# zx81_SD_11.net
KiCad netlist of a schematic drawn in EAGLE
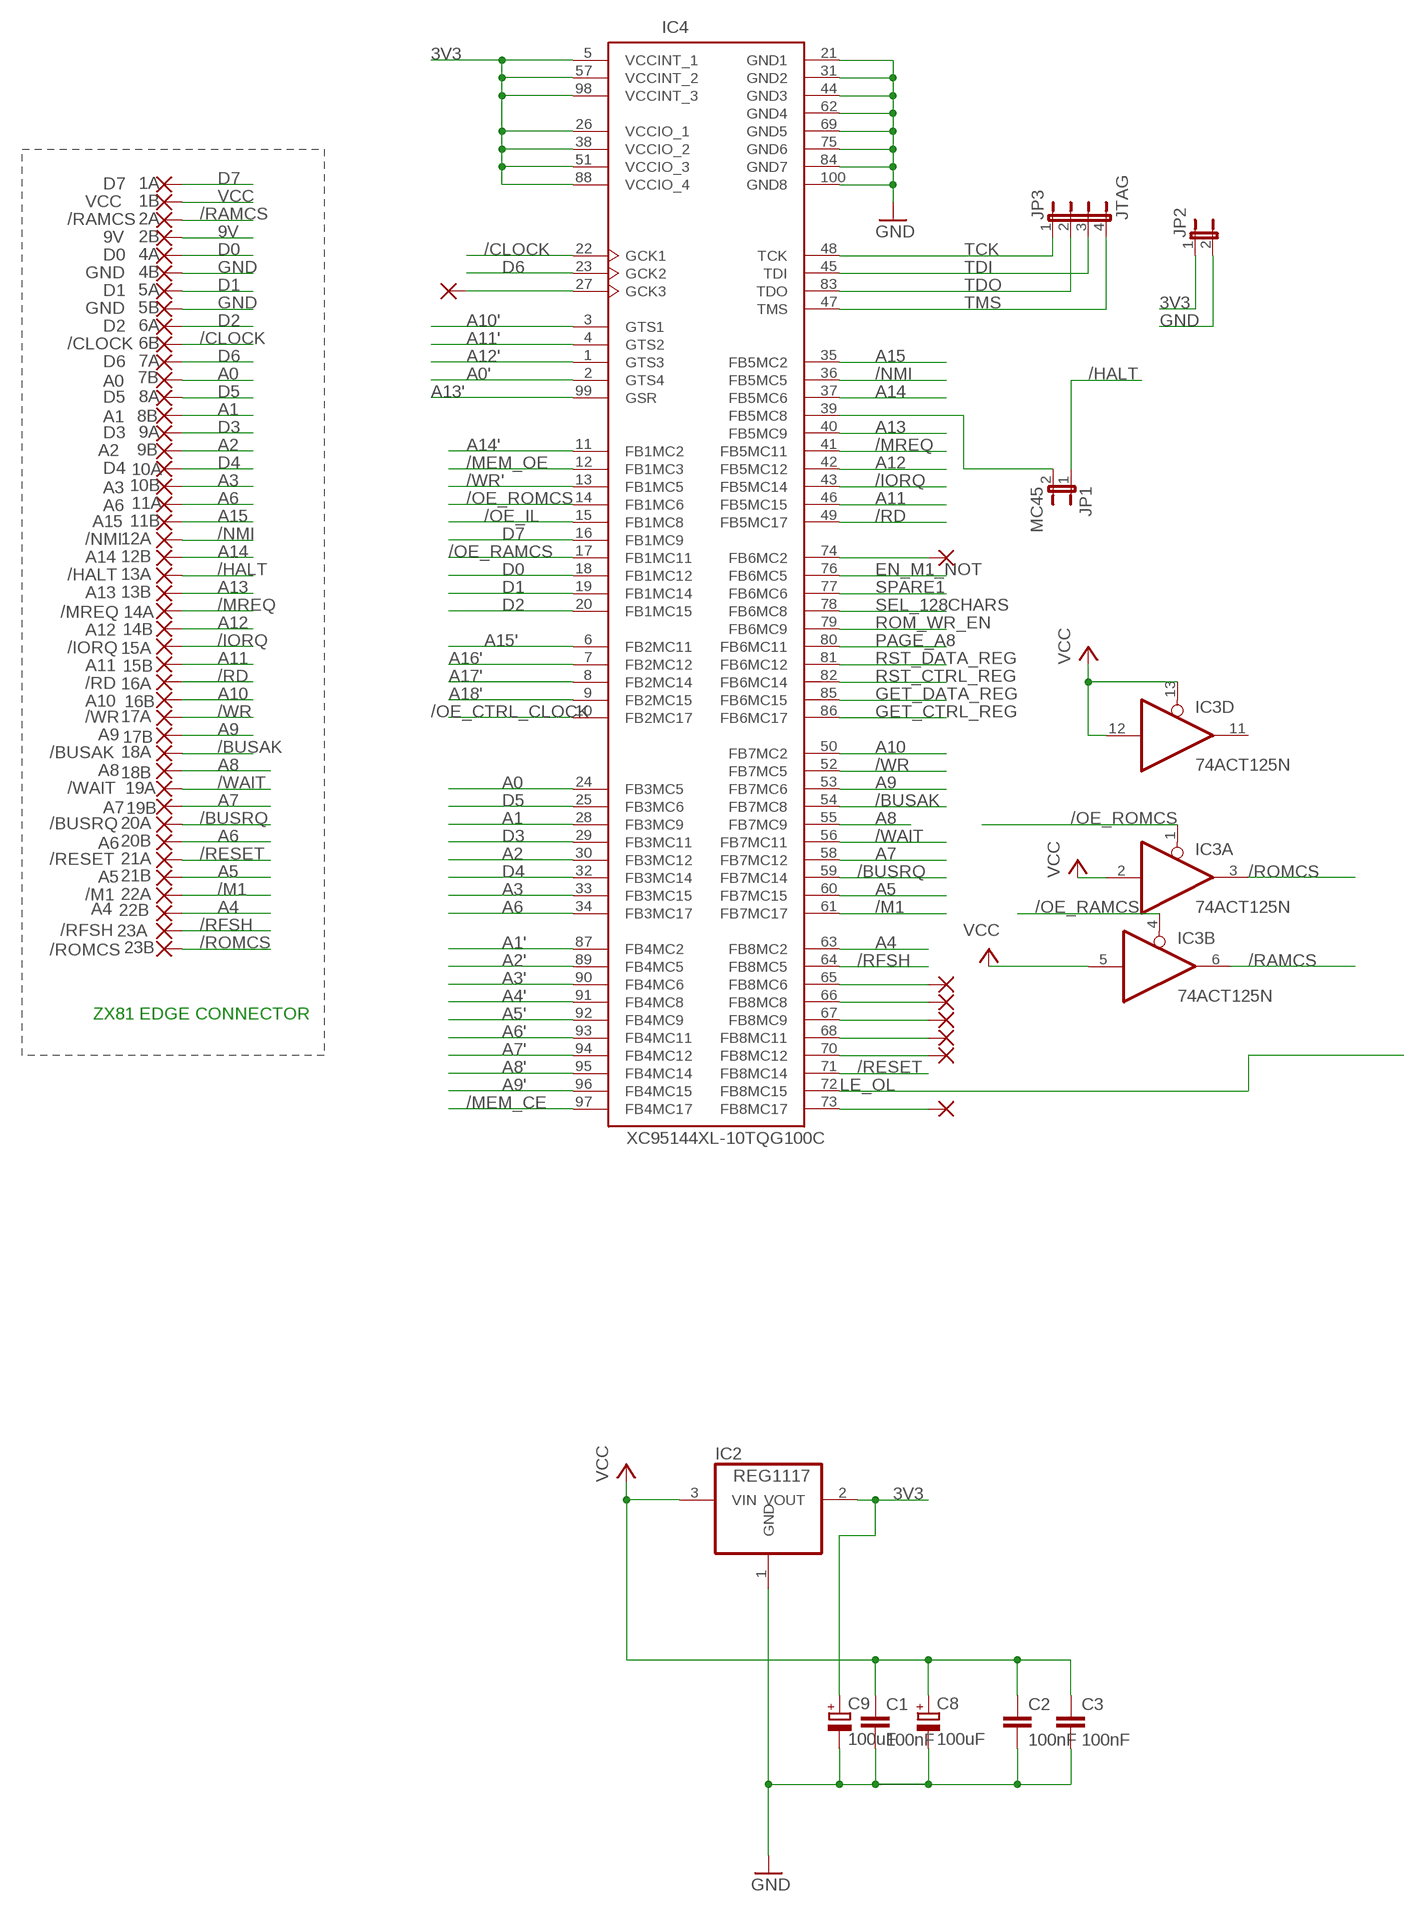
[diagram p0: schematic, sheet 1, part 1 of 2]
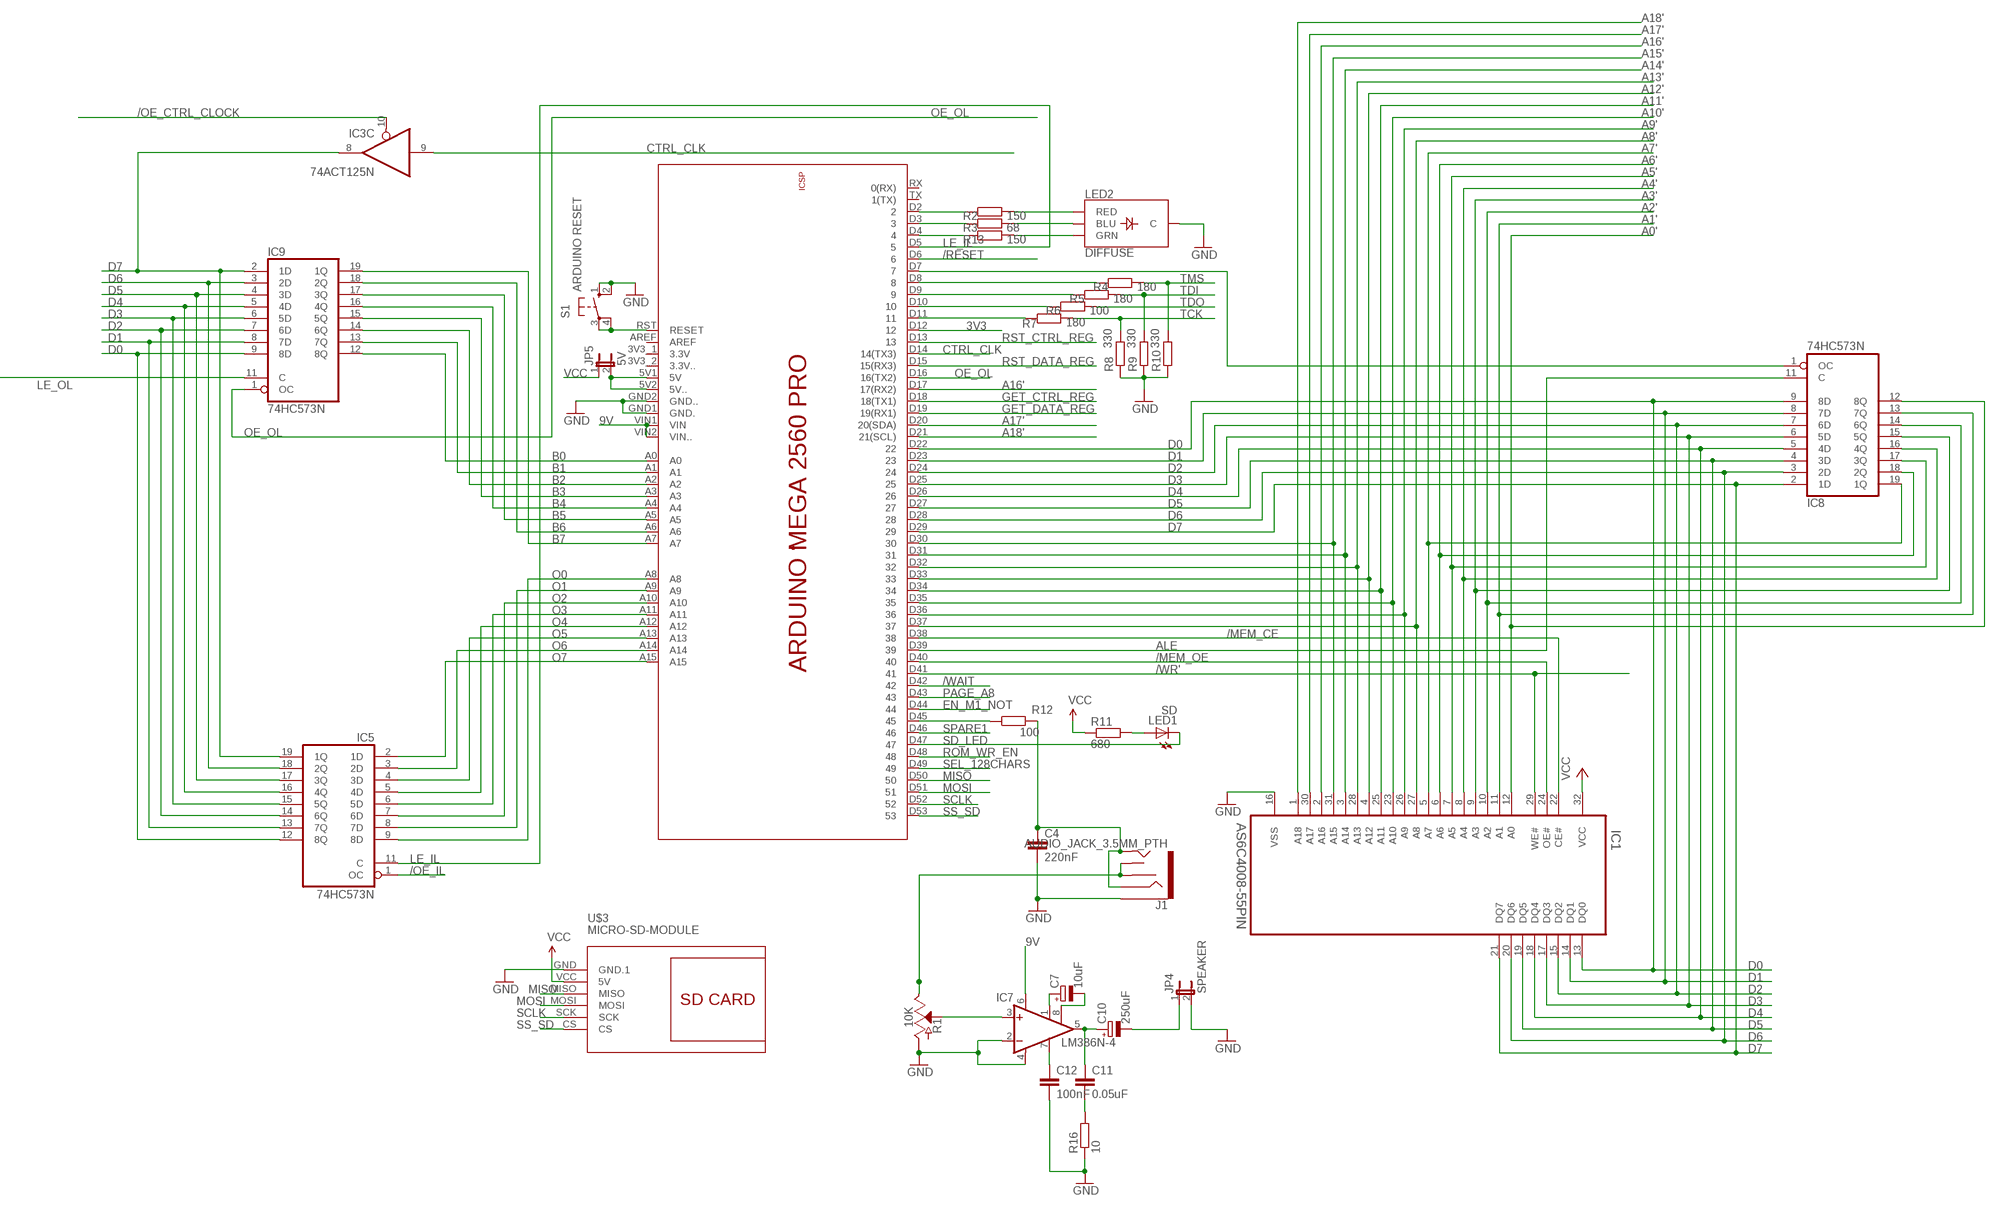
[diagram p1: schematic, sheet 1, part 2 of 2]

(export (version "E")
  (design (tool "Eeschema 10.0.6"))
  (components
    (comp (ref "1A")
      (value "D7")
      (footprint "eagle-import:EDGEPIN")
      (libsource (lib "eagle-import") (part "SMD2EDGEPIN"))
    )
    (comp (ref "1B")
      (value "VCC")
      (footprint "eagle-import:EDGEPIN")
      (libsource (lib "eagle-import") (part "SMD2EDGEPIN"))
    )
    (comp (ref "2A")
      (value "/RAMCS")
      (footprint "eagle-import:EDGEPIN")
      (libsource (lib "eagle-import") (part "SMD2EDGEPIN"))
    )
    (comp (ref "2B")
      (value "9V")
      (footprint "eagle-import:EDGEPIN")
      (libsource (lib "eagle-import") (part "SMD2EDGEPIN"))
    )
    (comp (ref "4A")
      (value "D0")
      (footprint "eagle-import:EDGEPIN")
      (libsource (lib "eagle-import") (part "SMD2EDGEPIN"))
    )
    (comp (ref "4B")
      (value "GND")
      (footprint "eagle-import:EDGEPIN")
      (libsource (lib "eagle-import") (part "SMD2EDGEPIN"))
    )
    (comp (ref "5A")
      (value "D1")
      (footprint "eagle-import:EDGEPIN")
      (libsource (lib "eagle-import") (part "SMD2EDGEPIN"))
    )
    (comp (ref "5B")
      (value "GND")
      (footprint "eagle-import:EDGEPIN")
      (libsource (lib "eagle-import") (part "SMD2EDGEPIN"))
    )
    (comp (ref "6A")
      (value "D2")
      (footprint "eagle-import:EDGEPIN")
      (libsource (lib "eagle-import") (part "SMD2EDGEPIN"))
    )
    (comp (ref "6B")
      (value "/CLOCK")
      (footprint "eagle-import:EDGEPIN")
      (libsource (lib "eagle-import") (part "SMD2EDGEPIN"))
    )
    (comp (ref "7A")
      (value "D6")
      (footprint "eagle-import:EDGEPIN")
      (libsource (lib "eagle-import") (part "SMD2EDGEPIN"))
    )
    (comp (ref "7B")
      (value "A0")
      (footprint "eagle-import:EDGEPIN")
      (libsource (lib "eagle-import") (part "SMD2EDGEPIN"))
    )
    (comp (ref "8A")
      (value "D5")
      (footprint "eagle-import:EDGEPIN")
      (libsource (lib "eagle-import") (part "SMD2EDGEPIN"))
    )
    (comp (ref "8B")
      (value "A1")
      (footprint "eagle-import:EDGEPIN")
      (libsource (lib "eagle-import") (part "SMD2EDGEPIN"))
    )
    (comp (ref "9A")
      (value "D3")
      (footprint "eagle-import:EDGEPIN")
      (libsource (lib "eagle-import") (part "SMD2EDGEPIN"))
    )
    (comp (ref "9B")
      (value "A2")
      (footprint "eagle-import:EDGEPIN")
      (libsource (lib "eagle-import") (part "SMD2EDGEPIN"))
    )
    (comp (ref "10A")
      (value "D4")
      (footprint "eagle-import:EDGEPIN")
      (libsource (lib "eagle-import") (part "SMD2EDGEPIN"))
    )
    (comp (ref "10B")
      (value "A3")
      (footprint "eagle-import:EDGEPIN")
      (libsource (lib "eagle-import") (part "SMD2EDGEPIN"))
    )
    (comp (ref "11A")
      (value "A6")
      (footprint "eagle-import:EDGEPIN")
      (libsource (lib "eagle-import") (part "SMD2EDGEPIN"))
    )
    (comp (ref "11B")
      (value "A15")
      (footprint "eagle-import:EDGEPIN")
      (libsource (lib "eagle-import") (part "SMD2EDGEPIN"))
    )
    (comp (ref "12A")
      (value "/NMI")
      (footprint "eagle-import:EDGEPIN")
      (libsource (lib "eagle-import") (part "SMD2EDGEPIN"))
    )
    (comp (ref "12B")
      (value "A14")
      (footprint "eagle-import:EDGEPIN")
      (libsource (lib "eagle-import") (part "SMD2EDGEPIN"))
    )
    (comp (ref "13A")
      (value "/HALT")
      (footprint "eagle-import:EDGEPIN")
      (libsource (lib "eagle-import") (part "SMD2EDGEPIN"))
    )
    (comp (ref "13B")
      (value "A13")
      (footprint "eagle-import:EDGEPIN")
      (libsource (lib "eagle-import") (part "SMD2EDGEPIN"))
    )
    (comp (ref "14A")
      (value "/MREQ")
      (footprint "eagle-import:EDGEPIN")
      (libsource (lib "eagle-import") (part "SMD2EDGEPIN"))
    )
    (comp (ref "14B")
      (value "A12")
      (footprint "eagle-import:EDGEPIN")
      (libsource (lib "eagle-import") (part "SMD2EDGEPIN"))
    )
    (comp (ref "15A")
      (value "/IORQ")
      (footprint "eagle-import:EDGEPIN")
      (libsource (lib "eagle-import") (part "SMD2EDGEPIN"))
    )
    (comp (ref "15B")
      (value "A11")
      (footprint "eagle-import:EDGEPIN")
      (libsource (lib "eagle-import") (part "SMD2EDGEPIN"))
    )
    (comp (ref "16A")
      (value "/RD")
      (footprint "eagle-import:EDGEPIN")
      (libsource (lib "eagle-import") (part "SMD2EDGEPIN"))
    )
    (comp (ref "16B")
      (value "A10")
      (footprint "eagle-import:EDGEPIN")
      (libsource (lib "eagle-import") (part "SMD2EDGEPIN"))
    )
    (comp (ref "17A")
      (value "/WR")
      (footprint "eagle-import:EDGEPIN")
      (libsource (lib "eagle-import") (part "SMD2EDGEPIN"))
    )
    (comp (ref "17B")
      (value "A9")
      (footprint "eagle-import:EDGEPIN")
      (libsource (lib "eagle-import") (part "SMD2EDGEPIN"))
    )
    (comp (ref "18A")
      (value "/BUSAK")
      (footprint "eagle-import:EDGEPIN")
      (libsource (lib "eagle-import") (part "SMD2EDGEPIN"))
    )
    (comp (ref "18B")
      (value "A8")
      (footprint "eagle-import:EDGEPIN")
      (libsource (lib "eagle-import") (part "SMD2EDGEPIN"))
    )
    (comp (ref "19A")
      (value "/WAIT")
      (footprint "eagle-import:EDGEPIN")
      (libsource (lib "eagle-import") (part "SMD2EDGEPIN"))
    )
    (comp (ref "19B")
      (value "A7")
      (footprint "eagle-import:EDGEPIN")
      (libsource (lib "eagle-import") (part "SMD2EDGEPIN"))
    )
    (comp (ref "20A")
      (value "/BUSRQ")
      (footprint "eagle-import:EDGEPIN")
      (libsource (lib "eagle-import") (part "SMD2EDGEPIN"))
    )
    (comp (ref "20B")
      (value "A6")
      (footprint "eagle-import:EDGEPIN")
      (libsource (lib "eagle-import") (part "SMD2EDGEPIN"))
    )
    (comp (ref "21A")
      (value "/RESET")
      (footprint "eagle-import:EDGEPIN")
      (libsource (lib "eagle-import") (part "SMD2EDGEPIN"))
    )
    (comp (ref "21B")
      (value "A5")
      (footprint "eagle-import:EDGEPIN")
      (libsource (lib "eagle-import") (part "SMD2EDGEPIN"))
    )
    (comp (ref "22A")
      (value "/M1")
      (footprint "eagle-import:EDGEPIN")
      (libsource (lib "eagle-import") (part "SMD2EDGEPIN"))
    )
    (comp (ref "22B")
      (value "A4")
      (footprint "eagle-import:EDGEPIN")
      (libsource (lib "eagle-import") (part "SMD2EDGEPIN"))
    )
    (comp (ref "23A")
      (value "/RFSH")
      (footprint "eagle-import:EDGEPIN")
      (libsource (lib "eagle-import") (part "SMD2EDGEPIN"))
    )
    (comp (ref "23B")
      (value "/ROMCS")
      (footprint "eagle-import:EDGEPIN")
      (libsource (lib "eagle-import") (part "SMD2EDGEPIN"))
    )
    (comp (ref "C1")
      (value "100nF")
      (footprint "eagle-import:C025-040X050")
      (libsource (lib "eagle-import") (part "C-EU025-040X050"))
    )
    (comp (ref "C2")
      (value "100nF")
      (footprint "eagle-import:C025-040X050")
      (libsource (lib "eagle-import") (part "C-EU025-040X050"))
    )
    (comp (ref "C3")
      (value "100nF")
      (footprint "eagle-import:C025-040X050")
      (libsource (lib "eagle-import") (part "C-EU025-040X050"))
    )
    (comp (ref "C4")
      (value "220nF")
      (footprint "eagle-import:C025-040X050")
      (libsource (lib "eagle-import") (part "C-EU025-040X050"))
    )
    (comp (ref "C7")
      (value "10uF")
      (footprint "eagle-import:E2-5")
      (libsource (lib "eagle-import") (part "CPOL-EUE2-5"))
    )
    (comp (ref "C8")
      (value "100uF")
      (footprint "eagle-import:E2-5")
      (libsource (lib "eagle-import") (part "CPOL-EUE2-5"))
    )
    (comp (ref "C9")
      (value "100uF")
      (footprint "eagle-import:E2-5")
      (libsource (lib "eagle-import") (part "CPOL-EUE2-5"))
    )
    (comp (ref "C10")
      (value "250uF")
      (footprint "eagle-import:E2-5")
      (libsource (lib "eagle-import") (part "CPOL-EUE2-5"))
    )
    (comp (ref "C11")
      (value "0.05uF")
      (footprint "eagle-import:C025-040X050")
      (libsource (lib "eagle-import") (part "C-EU025-040X050"))
    )
    (comp (ref "C12")
      (value "100nF")
      (footprint "eagle-import:C025-040X050")
      (libsource (lib "eagle-import") (part "C-EU025-040X050"))
    )
    (comp (ref "IC1")
      (value "AS6C4008-55PIN")
      (footprint "eagle-import:DIP1524W45P254L4203H406Q32")
      (fields (field (name "MF") "Alliance"))
      (libsource (lib "eagle-import") (part "AS6C4008-55PIN"))
    )
    (comp (ref "IC2")
      (value "REG1117")
      (footprint "eagle-import:SOT223")
      (libsource (lib "eagle-import") (part "REG1117"))
    )
    (comp (ref "IC3")
      (value "74ACT125N")
      (footprint "eagle-import:DIL14")
      (libsource (lib "eagle-import") (part "74125NACT"))
    )
    (comp (ref "IC4")
      (value "XC95144XL-10TQG100C")
      (footprint "eagle-import:TQFP100")
      (fields (field (name "MF") "Xilinx Inc."))
      (libsource (lib "eagle-import") (part "XC95144XL-10TQG100C"))
    )
    (comp (ref "IC5")
      (value "74HC573N")
      (footprint "eagle-import:DIL20")
      (libsource (lib "eagle-import") (part "74573NHC"))
    )
    (comp (ref "IC7")
      (value "LM386N-4")
      (footprint "eagle-import:DIL08")
      (libsource (lib "eagle-import") (part "LM386?-N4"))
    )
    (comp (ref "IC8")
      (value "74HC573N")
      (footprint "eagle-import:DIL20")
      (libsource (lib "eagle-import") (part "74573NHC"))
    )
    (comp (ref "IC9")
      (value "74HC573N")
      (footprint "eagle-import:DIL20")
      (libsource (lib "eagle-import") (part "74573NHC"))
    )
    (comp (ref "J1")
      (value "AUDIO_JACK_3.5MM_PTH")
      (footprint "eagle-import:AUDIO-JACK")
      (libsource (lib "eagle-import") (part "AUDIO_JACK_3.5MM_PTH"))
    )
    (comp (ref "JP1")
      (value "MC45")
      (footprint "eagle-import:JP1")
      (libsource (lib "eagle-import") (part "JP1E"))
    )
    (comp (ref "JP2")
      (value "JP1E")
      (footprint "eagle-import:JP1")
      (libsource (lib "eagle-import") (part "JP1E"))
    )
    (comp (ref "JP3")
      (value "JTAG")
      (footprint "eagle-import:JP4")
      (libsource (lib "eagle-import") (part "JP4E"))
    )
    (comp (ref "JP4")
      (value "SPEAKER")
      (footprint "eagle-import:JP1")
      (libsource (lib "eagle-import") (part "JP1E"))
    )
    (comp (ref "JP5")
      (value "5V")
      (footprint "eagle-import:JP1")
      (libsource (lib "eagle-import") (part "JP1E"))
    )
    (comp (ref "LED1")
      (value "SD")
      (footprint "eagle-import:LED5MM")
      (libsource (lib "eagle-import") (part "LED5MM"))
    )
    (comp (ref "LED2")
      (value "DIFFUSE")
      (footprint "eagle-import:LED-RGB-THRU")
      (libsource (lib "eagle-import") (part "LED-RGB-CCDIFFUSE"))
    )
    (comp (ref "PAD1")
      (value "1,6/0,8")
      (footprint "eagle-import:1,6_0,8")
      (libsource (lib "eagle-import") (part "1,6/0,8"))
    )
    (comp (ref "PAD2")
      (value "1,6/0,8")
      (footprint "eagle-import:1,6_0,8")
      (libsource (lib "eagle-import") (part "1,6/0,8"))
    )
    (comp (ref "PAD3")
      (value "1,6/0,8")
      (footprint "eagle-import:1,6_0,8")
      (libsource (lib "eagle-import") (part "1,6/0,8"))
    )
    (comp (ref "PAD4")
      (value "1,6/0,8")
      (footprint "eagle-import:1,6_0,8")
      (libsource (lib "eagle-import") (part "1,6/0,8"))
    )
    (comp (ref "PAD5")
      (value "1,6/0,8")
      (footprint "eagle-import:1,6_0,8")
      (libsource (lib "eagle-import") (part "1,6/0,8"))
    )
    (comp (ref "PAD6")
      (value "1,6/0,8")
      (footprint "eagle-import:1,6_0,8")
      (libsource (lib "eagle-import") (part "1,6/0,8"))
    )
    (comp (ref "PAD7")
      (value "1,6/0,8")
      (footprint "eagle-import:1,6_0,8")
      (libsource (lib "eagle-import") (part "1,6/0,8"))
    )
    (comp (ref "PAD8")
      (value "1,6/0,8")
      (footprint "eagle-import:1,6_0,8")
      (libsource (lib "eagle-import") (part "1,6/0,8"))
    )
    (comp (ref "R1")
      (value "10K")
      (footprint "eagle-import:POT-WHEEL")
      (libsource (lib "eagle-import") (part "POT"))
    )
    (comp (ref "R2")
      (value "150")
      (footprint "eagle-import:0204_7")
      (libsource (lib "eagle-import") (part "rcl_334_R-EU_0204/7"))
    )
    (comp (ref "R3")
      (value "68")
      (footprint "eagle-import:0204_7")
      (libsource (lib "eagle-import") (part "rcl_334_R-EU_0204/7"))
    )
    (comp (ref "R4")
      (value "180")
      (footprint "eagle-import:0204_7")
      (libsource (lib "eagle-import") (part "rcl_334_R-EU_0204/7"))
    )
    (comp (ref "R5")
      (value "180")
      (footprint "eagle-import:0204_7")
      (libsource (lib "eagle-import") (part "rcl_334_R-EU_0204/7"))
    )
    (comp (ref "R6")
      (value "100")
      (footprint "eagle-import:0204_7")
      (libsource (lib "eagle-import") (part "rcl_334_R-EU_0204/7"))
    )
    (comp (ref "R7")
      (value "180")
      (footprint "eagle-import:0204_7")
      (libsource (lib "eagle-import") (part "rcl_334_R-EU_0204/7"))
    )
    (comp (ref "R8")
      (value "330")
      (footprint "eagle-import:0204_7")
      (libsource (lib "eagle-import") (part "rcl_334_R-EU_0204/7"))
    )
    (comp (ref "R9")
      (value "330")
      (footprint "eagle-import:0204_7")
      (libsource (lib "eagle-import") (part "rcl_334_R-EU_0204/7"))
    )
    (comp (ref "R10")
      (value "330")
      (footprint "eagle-import:0204_7")
      (libsource (lib "eagle-import") (part "rcl_334_R-EU_0204/7"))
    )
    (comp (ref "R11")
      (value "680")
      (footprint "eagle-import:0204_7")
      (libsource (lib "eagle-import") (part "R-EU_0204/7"))
    )
    (comp (ref "R12")
      (value "100")
      (footprint "eagle-import:0204_7")
      (libsource (lib "eagle-import") (part "R-EU_0204/7"))
    )
    (comp (ref "R13")
      (value "150")
      (footprint "eagle-import:0204_7")
      (libsource (lib "eagle-import") (part "rcl_334_R-EU_0204/7"))
    )
    (comp (ref "R16")
      (value "10")
      (footprint "eagle-import:0204_7")
      (libsource (lib "eagle-import") (part "R-EU_0204/7"))
    )
    (comp (ref "S1")
      (value "ARDUINO RESET")
      (footprint "eagle-import:B3F-10XX")
      (fields (field (name "MPN") "B3F-1000"))
      (libsource (lib "eagle-import") (part "10-XX"))
    )
    (comp (ref "U$2")
      (value "E14_ARDUINO_REVC_ARDUINO_MEGA2560_PRO")
      (footprint "eagle-import:E14_ARDUINO_REVC_ARDUINO_MEGA2560_PRO")
      (libsource (lib "eagle-import") (part "E14_ARDUINO_REVC_ARDUINO_MEGA2560_PRO"))
    )
    (comp (ref "U$3")
      (value "MICRO-SD-MODULE")
      (footprint "eagle-import:MICROSD-MODULE")
      (libsource (lib "eagle-import") (part "MICRO-SD-MODULE"))
    )
  )
  (nets
    (net (code "1") (name "/3V3") (class "Default")
      (node (ref "C9") (pin "+") (pinfunction "+_+") (pintype "passive"))
      (node (ref "IC2") (pin "2") (pinfunction "VOUT_2") (pintype "output"))
      (node (ref "IC4") (pin "26") (pinfunction "VCCIO_1_26") (pintype "power_in"))
      (node (ref "IC4") (pin "38") (pinfunction "VCCIO_2_38") (pintype "power_in"))
      (node (ref "IC4") (pin "5") (pinfunction "VCCINT_1_5") (pintype "power_in"))
      (node (ref "IC4") (pin "51") (pinfunction "VCCIO_3_51") (pintype "power_in"))
      (node (ref "IC4") (pin "57") (pinfunction "VCCINT_2_57") (pintype "power_in"))
      (node (ref "IC4") (pin "88") (pinfunction "VCCIO_4_88") (pintype "power_in"))
      (node (ref "IC4") (pin "98") (pinfunction "VCCINT_3_98") (pintype "power_in"))
      (node (ref "JP2") (pin "1") (pinfunction "1_1") (pintype "passive"))
      (node (ref "U$2") (pin "D12") (pinfunction "12_D12") (pintype "bidirectional"))
    )
    (net (code "2") (name "/9V") (class "Default")
      (node (ref "2B") (pin "1") (pinfunction "P_1") (pintype "passive"))
      (node (ref "IC7") (pin "6") (pinfunction "VS_6") (pintype "power_in"))
      (node (ref "U$2") (pin "VIN1") (pinfunction "VIN_VIN1") (pintype "bidirectional"))
      (node (ref "U$2") (pin "VIN2") (pinfunction "VIN.._VIN2") (pintype "bidirectional"))
    )
    (net (code "3") (name "/A0") (class "Default")
      (node (ref "7B") (pin "1") (pinfunction "P_1") (pintype "passive"))
      (node (ref "IC4") (pin "24") (pinfunction "FB3MC5_24") (pintype "bidirectional"))
    )
    (net (code "4") (name "/A0'") (class "Default")
      (node (ref "IC1") (pin "12") (pinfunction "A0_12") (pintype "input"))
      (node (ref "IC4") (pin "2") (pinfunction "GTS4_2") (pintype "bidirectional"))
      (node (ref "IC8") (pin "12") (pinfunction "8Q_12") (pintype "tri_state"))
    )
    (net (code "5") (name "/A1") (class "Default")
      (node (ref "8B") (pin "1") (pinfunction "P_1") (pintype "passive"))
      (node (ref "IC4") (pin "28") (pinfunction "FB3MC9_28") (pintype "bidirectional"))
    )
    (net (code "6") (name "/A1'") (class "Default")
      (node (ref "IC1") (pin "11") (pinfunction "A1_11") (pintype "input"))
      (node (ref "IC4") (pin "87") (pinfunction "FB4MC2_87") (pintype "bidirectional"))
      (node (ref "IC8") (pin "13") (pinfunction "7Q_13") (pintype "tri_state"))
    )
    (net (code "7") (name "/A2") (class "Default")
      (node (ref "9B") (pin "1") (pinfunction "P_1") (pintype "passive"))
      (node (ref "IC4") (pin "30") (pinfunction "FB3MC12_30") (pintype "bidirectional"))
    )
    (net (code "8") (name "/A2'") (class "Default")
      (node (ref "IC1") (pin "10") (pinfunction "A2_10") (pintype "input"))
      (node (ref "IC4") (pin "89") (pinfunction "FB4MC5_89") (pintype "bidirectional"))
      (node (ref "IC8") (pin "14") (pinfunction "6Q_14") (pintype "tri_state"))
    )
    (net (code "9") (name "/A3") (class "Default")
      (node (ref "10B") (pin "1") (pinfunction "P_1") (pintype "passive"))
      (node (ref "IC4") (pin "33") (pinfunction "FB3MC15_33") (pintype "bidirectional"))
    )
    (net (code "10") (name "/A3'") (class "Default")
      (node (ref "IC1") (pin "9") (pinfunction "A3_9") (pintype "input"))
      (node (ref "IC4") (pin "90") (pinfunction "FB4MC6_90") (pintype "bidirectional"))
      (node (ref "IC8") (pin "15") (pinfunction "5Q_15") (pintype "tri_state"))
    )
    (net (code "11") (name "/A4") (class "Default")
      (node (ref "22B") (pin "1") (pinfunction "P_1") (pintype "passive"))
      (node (ref "IC4") (pin "63") (pinfunction "FB8MC2_63") (pintype "bidirectional"))
    )
    (net (code "12") (name "/A4'") (class "Default")
      (node (ref "IC1") (pin "8") (pinfunction "A4_8") (pintype "input"))
      (node (ref "IC4") (pin "91") (pinfunction "FB4MC8_91") (pintype "bidirectional"))
      (node (ref "IC8") (pin "16") (pinfunction "4Q_16") (pintype "tri_state"))
    )
    (net (code "13") (name "/A5") (class "Default")
      (node (ref "21B") (pin "1") (pinfunction "P_1") (pintype "passive"))
      (node (ref "IC4") (pin "60") (pinfunction "FB7MC15_60") (pintype "bidirectional"))
    )
    (net (code "14") (name "/A5'") (class "Default")
      (node (ref "IC1") (pin "7") (pinfunction "A5_7") (pintype "input"))
      (node (ref "IC4") (pin "92") (pinfunction "FB4MC9_92") (pintype "bidirectional"))
      (node (ref "IC8") (pin "17") (pinfunction "3Q_17") (pintype "tri_state"))
    )
    (net (code "15") (name "/A6") (class "Default")
      (node (ref "11A") (pin "1") (pinfunction "P_1") (pintype "passive"))
      (node (ref "20B") (pin "1") (pinfunction "P_1") (pintype "passive"))
      (node (ref "IC4") (pin "34") (pinfunction "FB3MC17_34") (pintype "bidirectional"))
    )
    (net (code "16") (name "/A6'") (class "Default")
      (node (ref "IC1") (pin "6") (pinfunction "A6_6") (pintype "input"))
      (node (ref "IC4") (pin "93") (pinfunction "FB4MC11_93") (pintype "bidirectional"))
      (node (ref "IC8") (pin "18") (pinfunction "2Q_18") (pintype "tri_state"))
    )
    (net (code "17") (name "/A7") (class "Default")
      (node (ref "19B") (pin "1") (pinfunction "P_1") (pintype "passive"))
      (node (ref "IC4") (pin "58") (pinfunction "FB7MC12_58") (pintype "bidirectional"))
    )
    (net (code "18") (name "/A7'") (class "Default")
      (node (ref "IC1") (pin "5") (pinfunction "A7_5") (pintype "input"))
      (node (ref "IC4") (pin "94") (pinfunction "FB4MC12_94") (pintype "bidirectional"))
      (node (ref "IC8") (pin "19") (pinfunction "1Q_19") (pintype "tri_state"))
    )
    (net (code "19") (name "/A8") (class "Default")
      (node (ref "18B") (pin "1") (pinfunction "P_1") (pintype "passive"))
      (node (ref "IC4") (pin "55") (pinfunction "FB7MC9_55") (pintype "bidirectional"))
    )
    (net (code "20") (name "/A8'") (class "Default")
      (node (ref "IC1") (pin "27") (pinfunction "A8_27") (pintype "input"))
      (node (ref "IC4") (pin "95") (pinfunction "FB4MC14_95") (pintype "bidirectional"))
      (node (ref "U$2") (pin "D37") (pinfunction "37_D37") (pintype "bidirectional"))
    )
    (net (code "21") (name "/A9") (class "Default")
      (node (ref "17B") (pin "1") (pinfunction "P_1") (pintype "passive"))
      (node (ref "IC4") (pin "53") (pinfunction "FB7MC6_53") (pintype "bidirectional"))
    )
    (net (code "22") (name "/A9'") (class "Default")
      (node (ref "IC1") (pin "26") (pinfunction "A9_26") (pintype "input"))
      (node (ref "IC4") (pin "96") (pinfunction "FB4MC15_96") (pintype "bidirectional"))
      (node (ref "U$2") (pin "D36") (pinfunction "36_D36") (pintype "bidirectional"))
    )
    (net (code "23") (name "/A10") (class "Default")
      (node (ref "16B") (pin "1") (pinfunction "P_1") (pintype "passive"))
      (node (ref "IC4") (pin "50") (pinfunction "FB7MC2_50") (pintype "bidirectional"))
    )
    (net (code "24") (name "/A10'") (class "Default")
      (node (ref "IC1") (pin "23") (pinfunction "A10_23") (pintype "input"))
      (node (ref "IC4") (pin "3") (pinfunction "GTS1_3") (pintype "bidirectional"))
      (node (ref "U$2") (pin "D35") (pinfunction "35_D35") (pintype "bidirectional"))
    )
    (net (code "25") (name "/A11") (class "Default")
      (node (ref "15B") (pin "1") (pinfunction "P_1") (pintype "passive"))
      (node (ref "IC4") (pin "46") (pinfunction "FB5MC15_46") (pintype "bidirectional"))
    )
    (net (code "26") (name "/A11'") (class "Default")
      (node (ref "IC1") (pin "25") (pinfunction "A11_25") (pintype "input"))
      (node (ref "IC4") (pin "4") (pinfunction "GTS2_4") (pintype "bidirectional"))
      (node (ref "U$2") (pin "D34") (pinfunction "34_D34") (pintype "bidirectional"))
    )
    (net (code "27") (name "/A12") (class "Default")
      (node (ref "14B") (pin "1") (pinfunction "P_1") (pintype "passive"))
      (node (ref "IC4") (pin "42") (pinfunction "FB5MC12_42") (pintype "bidirectional"))
    )
    (net (code "28") (name "/A12'") (class "Default")
      (node (ref "IC1") (pin "4") (pinfunction "A12_4") (pintype "input"))
      (node (ref "IC4") (pin "1") (pinfunction "GTS3_1") (pintype "bidirectional"))
      (node (ref "U$2") (pin "D33") (pinfunction "33_D33") (pintype "bidirectional"))
    )
    (net (code "29") (name "/A13") (class "Default")
      (node (ref "13B") (pin "1") (pinfunction "P_1") (pintype "passive"))
      (node (ref "IC4") (pin "40") (pinfunction "FB5MC9_40") (pintype "bidirectional"))
    )
    (net (code "30") (name "/A13'") (class "Default")
      (node (ref "IC1") (pin "28") (pinfunction "A13_28") (pintype "input"))
      (node (ref "IC4") (pin "99") (pinfunction "GSR_99") (pintype "bidirectional"))
      (node (ref "U$2") (pin "D32") (pinfunction "32_D32") (pintype "bidirectional"))
    )
    (net (code "31") (name "/A14") (class "Default")
      (node (ref "12B") (pin "1") (pinfunction "P_1") (pintype "passive"))
      (node (ref "IC4") (pin "37") (pinfunction "FB5MC6_37") (pintype "bidirectional"))
    )
    (net (code "32") (name "/A14'") (class "Default")
      (node (ref "IC1") (pin "3") (pinfunction "A14_3") (pintype "input"))
      (node (ref "IC4") (pin "11") (pinfunction "FB1MC2_11") (pintype "bidirectional"))
      (node (ref "U$2") (pin "D31") (pinfunction "31_D31") (pintype "bidirectional"))
    )
    (net (code "33") (name "/A15") (class "Default")
      (node (ref "11B") (pin "1") (pinfunction "P_1") (pintype "passive"))
      (node (ref "IC4") (pin "35") (pinfunction "FB5MC2_35") (pintype "bidirectional"))
    )
    (net (code "34") (name "/A15'") (class "Default")
      (node (ref "IC1") (pin "31") (pinfunction "A15_31") (pintype "input"))
      (node (ref "IC4") (pin "6") (pinfunction "FB2MC11_6") (pintype "bidirectional"))
      (node (ref "U$2") (pin "D30") (pinfunction "30_D30") (pintype "bidirectional"))
    )
    (net (code "35") (name "/A16'") (class "Default")
      (node (ref "IC1") (pin "2") (pinfunction "A16_2") (pintype "input"))
      (node (ref "IC4") (pin "7") (pinfunction "FB2MC12_7") (pintype "bidirectional"))
      (node (ref "U$2") (pin "D17") (pinfunction "17(RX2)_D17") (pintype "bidirectional"))
    )
    (net (code "36") (name "/A17'") (class "Default")
      (node (ref "IC1") (pin "30") (pinfunction "A17_30") (pintype "input"))
      (node (ref "IC4") (pin "8") (pinfunction "FB2MC14_8") (pintype "bidirectional"))
      (node (ref "U$2") (pin "D20") (pinfunction "20(SDA)_D20") (pintype "bidirectional"))
    )
    (net (code "37") (name "/A18'") (class "Default")
      (node (ref "IC1") (pin "1") (pinfunction "A18_1") (pintype "input"))
      (node (ref "IC4") (pin "9") (pinfunction "FB2MC15_9") (pintype "bidirectional"))
      (node (ref "U$2") (pin "D21") (pinfunction "21(SCL)_D21") (pintype "bidirectional"))
    )
    (net (code "38") (name "/ALE") (class "Default")
      (node (ref "IC8") (pin "11") (pinfunction "C_11") (pintype "input"))
      (node (ref "U$2") (pin "D39") (pinfunction "39_D39") (pintype "bidirectional"))
    )
    (net (code "39") (name "/B0") (class "Default")
      (node (ref "IC9") (pin "19") (pinfunction "1Q_19") (pintype "tri_state"))
      (node (ref "U$2") (pin "A7") (pinfunction "A7_A7") (pintype "bidirectional"))
    )
    (net (code "40") (name "/B1") (class "Default")
      (node (ref "IC9") (pin "18") (pinfunction "2Q_18") (pintype "tri_state"))
      (node (ref "U$2") (pin "A6") (pinfunction "A6_A6") (pintype "bidirectional"))
    )
    (net (code "41") (name "/B2") (class "Default")
      (node (ref "IC9") (pin "17") (pinfunction "3Q_17") (pintype "tri_state"))
      (node (ref "U$2") (pin "A5") (pinfunction "A5_A5") (pintype "bidirectional"))
    )
    (net (code "42") (name "/B3") (class "Default")
      (node (ref "IC9") (pin "16") (pinfunction "4Q_16") (pintype "tri_state"))
      (node (ref "U$2") (pin "A4") (pinfunction "A4_A4") (pintype "bidirectional"))
    )
    (net (code "43") (name "/B4") (class "Default")
      (node (ref "IC9") (pin "15") (pinfunction "5Q_15") (pintype "tri_state"))
      (node (ref "U$2") (pin "A3") (pinfunction "A3_A3") (pintype "bidirectional"))
    )
    (net (code "44") (name "/B5") (class "Default")
      (node (ref "IC9") (pin "14") (pinfunction "6Q_14") (pintype "tri_state"))
      (node (ref "U$2") (pin "A2") (pinfunction "A2_A2") (pintype "bidirectional"))
    )
    (net (code "45") (name "/B6") (class "Default")
      (node (ref "IC9") (pin "13") (pinfunction "7Q_13") (pintype "tri_state"))
      (node (ref "U$2") (pin "A1") (pinfunction "A1_A1") (pintype "bidirectional"))
    )
    (net (code "46") (name "/B7") (class "Default")
      (node (ref "IC9") (pin "12") (pinfunction "8Q_12") (pintype "tri_state"))
      (node (ref "U$2") (pin "A0") (pinfunction "A0_A0") (pintype "bidirectional"))
    )
    (net (code "47") (name "/CTRL_CLK") (class "Default")
      (node (ref "IC3") (pin "9") (pinfunction "I_9") (pintype "input"))
      (node (ref "U$2") (pin "D14") (pinfunction "14(TX3)_D14") (pintype "bidirectional"))
    )
    (net (code "48") (name "/D0") (class "Default")
      (node (ref "4A") (pin "1") (pinfunction "P_1") (pintype "passive"))
      (node (ref "IC1") (pin "13") (pinfunction "DQ0_13") (pintype "bidirectional"))
      (node (ref "IC4") (pin "18") (pinfunction "FB1MC12_18") (pintype "bidirectional"))
      (node (ref "IC5") (pin "12") (pinfunction "8Q_12") (pintype "tri_state"))
      (node (ref "IC8") (pin "9") (pinfunction "8D_9") (pintype "input"))
      (node (ref "IC9") (pin "9") (pinfunction "8D_9") (pintype "input"))
      (node (ref "U$2") (pin "D22") (pinfunction "22_D22") (pintype "bidirectional"))
    )
    (net (code "49") (name "/D1") (class "Default")
      (node (ref "5A") (pin "1") (pinfunction "P_1") (pintype "passive"))
      (node (ref "IC1") (pin "14") (pinfunction "DQ1_14") (pintype "bidirectional"))
      (node (ref "IC4") (pin "19") (pinfunction "FB1MC14_19") (pintype "bidirectional"))
      (node (ref "IC5") (pin "13") (pinfunction "7Q_13") (pintype "tri_state"))
      (node (ref "IC8") (pin "8") (pinfunction "7D_8") (pintype "input"))
      (node (ref "IC9") (pin "8") (pinfunction "7D_8") (pintype "input"))
      (node (ref "U$2") (pin "D23") (pinfunction "23_D23") (pintype "bidirectional"))
    )
    (net (code "50") (name "/D2") (class "Default")
      (node (ref "6A") (pin "1") (pinfunction "P_1") (pintype "passive"))
      (node (ref "IC1") (pin "15") (pinfunction "DQ2_15") (pintype "bidirectional"))
      (node (ref "IC4") (pin "20") (pinfunction "FB1MC15_20") (pintype "bidirectional"))
      (node (ref "IC5") (pin "14") (pinfunction "6Q_14") (pintype "tri_state"))
      (node (ref "IC8") (pin "7") (pinfunction "6D_7") (pintype "input"))
      (node (ref "IC9") (pin "7") (pinfunction "6D_7") (pintype "input"))
      (node (ref "U$2") (pin "D24") (pinfunction "24_D24") (pintype "bidirectional"))
    )
    (net (code "51") (name "/D3") (class "Default")
      (node (ref "9A") (pin "1") (pinfunction "P_1") (pintype "passive"))
      (node (ref "IC1") (pin "17") (pinfunction "DQ3_17") (pintype "bidirectional"))
      (node (ref "IC4") (pin "29") (pinfunction "FB3MC11_29") (pintype "bidirectional"))
      (node (ref "IC5") (pin "15") (pinfunction "5Q_15") (pintype "tri_state"))
      (node (ref "IC8") (pin "6") (pinfunction "5D_6") (pintype "input"))
      (node (ref "IC9") (pin "6") (pinfunction "5D_6") (pintype "input"))
      (node (ref "U$2") (pin "D25") (pinfunction "25_D25") (pintype "bidirectional"))
    )
    (net (code "52") (name "/D4") (class "Default")
      (node (ref "10A") (pin "1") (pinfunction "P_1") (pintype "passive"))
      (node (ref "IC1") (pin "18") (pinfunction "DQ4_18") (pintype "bidirectional"))
      (node (ref "IC4") (pin "32") (pinfunction "FB3MC14_32") (pintype "bidirectional"))
      (node (ref "IC5") (pin "16") (pinfunction "4Q_16") (pintype "tri_state"))
      (node (ref "IC8") (pin "5") (pinfunction "4D_5") (pintype "input"))
      (node (ref "IC9") (pin "5") (pinfunction "4D_5") (pintype "input"))
      (node (ref "U$2") (pin "D26") (pinfunction "26_D26") (pintype "bidirectional"))
    )
    (net (code "53") (name "/D5") (class "Default")
      (node (ref "8A") (pin "1") (pinfunction "P_1") (pintype "passive"))
      (node (ref "IC1") (pin "19") (pinfunction "DQ5_19") (pintype "bidirectional"))
      (node (ref "IC4") (pin "25") (pinfunction "FB3MC6_25") (pintype "bidirectional"))
      (node (ref "IC5") (pin "17") (pinfunction "3Q_17") (pintype "tri_state"))
      (node (ref "IC8") (pin "4") (pinfunction "3D_4") (pintype "input"))
      (node (ref "IC9") (pin "4") (pinfunction "3D_4") (pintype "input"))
      (node (ref "U$2") (pin "D27") (pinfunction "27_D27") (pintype "bidirectional"))
    )
    (net (code "54") (name "/D6") (class "Default")
      (node (ref "7A") (pin "1") (pinfunction "P_1") (pintype "passive"))
      (node (ref "IC1") (pin "20") (pinfunction "DQ6_20") (pintype "bidirectional"))
      (node (ref "IC4") (pin "23") (pinfunction "GCK2_23") (pintype "bidirectional"))
      (node (ref "IC5") (pin "18") (pinfunction "2Q_18") (pintype "tri_state"))
      (node (ref "IC8") (pin "3") (pinfunction "2D_3") (pintype "input"))
      (node (ref "IC9") (pin "3") (pinfunction "2D_3") (pintype "input"))
      (node (ref "U$2") (pin "D28") (pinfunction "28_D28") (pintype "bidirectional"))
    )
    (net (code "55") (name "/D7") (class "Default")
      (node (ref "1A") (pin "1") (pinfunction "P_1") (pintype "passive"))
      (node (ref "IC1") (pin "21") (pinfunction "DQ7_21") (pintype "bidirectional"))
      (node (ref "IC3") (pin "8") (pinfunction "O_8") (pintype "tri_state"))
      (node (ref "IC4") (pin "16") (pinfunction "FB1MC9_16") (pintype "bidirectional"))
      (node (ref "IC5") (pin "19") (pinfunction "1Q_19") (pintype "tri_state"))
      (node (ref "IC8") (pin "2") (pinfunction "1D_2") (pintype "input"))
      (node (ref "IC9") (pin "2") (pinfunction "1D_2") (pintype "input"))
      (node (ref "U$2") (pin "D29") (pinfunction "29_D29") (pintype "bidirectional"))
    )
    (net (code "56") (name "/EN_M1_NOT") (class "Default")
      (node (ref "IC4") (pin "76") (pinfunction "FB6MC5_76") (pintype "bidirectional"))
      (node (ref "U$2") (pin "D44") (pinfunction "44_D44") (pintype "bidirectional"))
    )
    (net (code "57") (name "/GET_CTRL_REG") (class "Default")
      (node (ref "IC4") (pin "86") (pinfunction "FB6MC17_86") (pintype "bidirectional"))
      (node (ref "U$2") (pin "D18") (pinfunction "18(TX1)_D18") (pintype "bidirectional"))
    )
    (net (code "58") (name "/GET_DATA_REG") (class "Default")
      (node (ref "IC4") (pin "85") (pinfunction "FB6MC15_85") (pintype "bidirectional"))
      (node (ref "U$2") (pin "D19") (pinfunction "19(RX1)_D19") (pintype "bidirectional"))
    )
    (net (code "59") (name "/LE_IL") (class "Default")
      (node (ref "IC5") (pin "11") (pinfunction "C_11") (pintype "input"))
      (node (ref "U$2") (pin "D5") (pinfunction "5_D5") (pintype "bidirectional"))
    )
    (net (code "60") (name "/LE_OL") (class "Default")
      (node (ref "IC4") (pin "72") (pinfunction "FB8MC15_72") (pintype "bidirectional"))
      (node (ref "IC9") (pin "11") (pinfunction "C_11") (pintype "input"))
    )
    (net (code "61") (name "/MISO") (class "Default")
      (node (ref "U$2") (pin "D50") (pinfunction "50_D50") (pintype "bidirectional"))
      (node (ref "U$3") (pin "MISO") (pinfunction "MISO_MISO") (pintype "bidirectional"))
    )
    (net (code "62") (name "/MOSI") (class "Default")
      (node (ref "U$2") (pin "D51") (pinfunction "51_D51") (pintype "bidirectional"))
      (node (ref "U$3") (pin "MOSI") (pinfunction "MOSI_MOSI") (pintype "bidirectional"))
    )
    (net (code "63") (name "/O0") (class "Default")
      (node (ref "IC5") (pin "2") (pinfunction "1D_2") (pintype "input"))
      (node (ref "U$2") (pin "A15") (pinfunction "A15_A15") (pintype "bidirectional"))
    )
    (net (code "64") (name "/O1") (class "Default")
      (node (ref "IC5") (pin "3") (pinfunction "2D_3") (pintype "input"))
      (node (ref "U$2") (pin "A14") (pinfunction "A14_A14") (pintype "bidirectional"))
    )
    (net (code "65") (name "/O2") (class "Default")
      (node (ref "IC5") (pin "4") (pinfunction "3D_4") (pintype "input"))
      (node (ref "U$2") (pin "A13") (pinfunction "A13_A13") (pintype "bidirectional"))
    )
    (net (code "66") (name "/O3") (class "Default")
      (node (ref "IC5") (pin "5") (pinfunction "4D_5") (pintype "input"))
      (node (ref "U$2") (pin "A12") (pinfunction "A12_A12") (pintype "bidirectional"))
    )
    (net (code "67") (name "/O4") (class "Default")
      (node (ref "IC5") (pin "6") (pinfunction "5D_6") (pintype "input"))
      (node (ref "U$2") (pin "A11") (pinfunction "A11_A11") (pintype "bidirectional"))
    )
    (net (code "68") (name "/O5") (class "Default")
      (node (ref "IC5") (pin "7") (pinfunction "6D_7") (pintype "input"))
      (node (ref "U$2") (pin "A10") (pinfunction "A10_A10") (pintype "bidirectional"))
    )
    (net (code "69") (name "/O6") (class "Default")
      (node (ref "IC5") (pin "8") (pinfunction "7D_8") (pintype "input"))
      (node (ref "U$2") (pin "A9") (pinfunction "A9_A9") (pintype "bidirectional"))
    )
    (net (code "70") (name "/O7") (class "Default")
      (node (ref "IC5") (pin "9") (pinfunction "8D_9") (pintype "input"))
      (node (ref "U$2") (pin "A8") (pinfunction "A8_A8") (pintype "bidirectional"))
    )
    (net (code "71") (name "/OE_OL") (class "Default")
      (node (ref "IC9") (pin "1") (pinfunction "OC_1") (pintype "input"))
      (node (ref "U$2") (pin "D16") (pinfunction "16(TX2)_D16") (pintype "bidirectional"))
    )
    (net (code "72") (name "/PAGE_A8") (class "Default")
      (node (ref "IC4") (pin "80") (pinfunction "FB6MC11_80") (pintype "bidirectional"))
      (node (ref "U$2") (pin "D43") (pinfunction "43_D43") (pintype "bidirectional"))
    )
    (net (code "73") (name "/ROM_WR_EN") (class "Default")
      (node (ref "IC4") (pin "79") (pinfunction "FB6MC9_79") (pintype "bidirectional"))
      (node (ref "U$2") (pin "D48") (pinfunction "48_D48") (pintype "bidirectional"))
    )
    (net (code "74") (name "/RST_CTRL_REG") (class "Default")
      (node (ref "IC4") (pin "82") (pinfunction "FB6MC14_82") (pintype "bidirectional"))
      (node (ref "U$2") (pin "D13") (pinfunction "13_D13") (pintype "bidirectional"))
    )
    (net (code "75") (name "/RST_DATA_REG") (class "Default")
      (node (ref "IC4") (pin "81") (pinfunction "FB6MC12_81") (pintype "bidirectional"))
      (node (ref "U$2") (pin "D15") (pinfunction "15(RX3)_D15") (pintype "bidirectional"))
    )
    (net (code "76") (name "/SCLK") (class "Default")
      (node (ref "U$2") (pin "D52") (pinfunction "52_D52") (pintype "bidirectional"))
      (node (ref "U$3") (pin "SCK") (pinfunction "SCK_SCK") (pintype "bidirectional"))
    )
    (net (code "77") (name "/SD_LED") (class "Default")
      (node (ref "LED1") (pin "K") (pinfunction "C_K") (pintype "passive"))
      (node (ref "U$2") (pin "D47") (pinfunction "47_D47") (pintype "bidirectional"))
    )
    (net (code "78") (name "/SEL_128CHARS") (class "Default")
      (node (ref "IC4") (pin "78") (pinfunction "FB6MC8_78") (pintype "bidirectional"))
      (node (ref "U$2") (pin "D49") (pinfunction "49_D49") (pintype "bidirectional"))
    )
    (net (code "79") (name "/SPARE1") (class "Default")
      (node (ref "IC4") (pin "77") (pinfunction "FB6MC6_77") (pintype "bidirectional"))
      (node (ref "U$2") (pin "D46") (pinfunction "46_D46") (pintype "bidirectional"))
    )
    (net (code "80") (name "/SS_SD") (class "Default")
      (node (ref "U$2") (pin "D53") (pinfunction "53_D53") (pintype "bidirectional"))
      (node (ref "U$3") (pin "CS") (pinfunction "CS_CS") (pintype "bidirectional"))
    )
    (net (code "81") (name "/TCK") (class "Default")
      (node (ref "IC4") (pin "48") (pinfunction "TCK_48") (pintype "passive"))
      (node (ref "JP3") (pin "1") (pinfunction "1_1") (pintype "passive"))
      (node (ref "R7") (pin "2") (pinfunction "2_2") (pintype "passive"))
      (node (ref "R8") (pin "2") (pinfunction "2_2") (pintype "passive"))
    )
    (net (code "82") (name "/TDI") (class "Default")
      (node (ref "IC4") (pin "45") (pinfunction "TDI_45") (pintype "passive"))
      (node (ref "JP3") (pin "3") (pinfunction "3_3") (pintype "passive"))
      (node (ref "R5") (pin "2") (pinfunction "2_2") (pintype "passive"))
      (node (ref "R9") (pin "2") (pinfunction "2_2") (pintype "passive"))
    )
    (net (code "83") (name "/TDO") (class "Default")
      (node (ref "IC4") (pin "83") (pinfunction "TDO_83") (pintype "passive"))
      (node (ref "JP3") (pin "2") (pinfunction "2_2") (pintype "passive"))
      (node (ref "R6") (pin "2") (pinfunction "2_2") (pintype "passive"))
    )
    (net (code "84") (name "/TMS") (class "Default")
      (node (ref "IC4") (pin "47") (pinfunction "TMS_47") (pintype "passive"))
      (node (ref "JP3") (pin "4") (pinfunction "4_4") (pintype "passive"))
      (node (ref "R10") (pin "2") (pinfunction "2_2") (pintype "passive"))
      (node (ref "R4") (pin "2") (pinfunction "2_2") (pintype "passive"))
    )
    (net (code "85") (name "/{slash}BUSAK") (class "Default")
      (node (ref "18A") (pin "1") (pinfunction "P_1") (pintype "passive"))
      (node (ref "IC4") (pin "54") (pinfunction "FB7MC8_54") (pintype "bidirectional"))
    )
    (net (code "86") (name "/{slash}BUSRQ") (class "Default")
      (node (ref "20A") (pin "1") (pinfunction "P_1") (pintype "passive"))
      (node (ref "IC4") (pin "59") (pinfunction "FB7MC14_59") (pintype "bidirectional"))
    )
    (net (code "87") (name "/{slash}CLOCK") (class "Default")
      (node (ref "6B") (pin "1") (pinfunction "P_1") (pintype "passive"))
      (node (ref "IC4") (pin "22") (pinfunction "GCK1_22") (pintype "bidirectional"))
    )
    (net (code "88") (name "/{slash}HALT") (class "Default")
      (node (ref "13A") (pin "1") (pinfunction "P_1") (pintype "passive"))
      (node (ref "JP1") (pin "1") (pinfunction "1_1") (pintype "passive"))
    )
    (net (code "89") (name "/{slash}IORQ") (class "Default")
      (node (ref "15A") (pin "1") (pinfunction "P_1") (pintype "passive"))
      (node (ref "IC4") (pin "43") (pinfunction "FB5MC14_43") (pintype "bidirectional"))
    )
    (net (code "90") (name "/{slash}M1") (class "Default")
      (node (ref "22A") (pin "1") (pinfunction "P_1") (pintype "passive"))
      (node (ref "IC4") (pin "61") (pinfunction "FB7MC17_61") (pintype "bidirectional"))
    )
    (net (code "91") (name "/{slash}MEM_CE") (class "Default")
      (node (ref "IC1") (pin "22") (pinfunction "CE#_22") (pintype "input"))
      (node (ref "IC4") (pin "97") (pinfunction "FB4MC17_97") (pintype "bidirectional"))
      (node (ref "U$2") (pin "D38") (pinfunction "38_D38") (pintype "bidirectional"))
    )
    (net (code "92") (name "/{slash}MEM_OE") (class "Default")
      (node (ref "IC1") (pin "24") (pinfunction "OE#_24") (pintype "input"))
      (node (ref "IC4") (pin "12") (pinfunction "FB1MC3_12") (pintype "bidirectional"))
      (node (ref "U$2") (pin "D40") (pinfunction "40_D40") (pintype "bidirectional"))
    )
    (net (code "93") (name "/{slash}MREQ") (class "Default")
      (node (ref "14A") (pin "1") (pinfunction "P_1") (pintype "passive"))
      (node (ref "IC4") (pin "41") (pinfunction "FB5MC11_41") (pintype "bidirectional"))
    )
    (net (code "94") (name "/{slash}NMI") (class "Default")
      (node (ref "12A") (pin "1") (pinfunction "P_1") (pintype "passive"))
      (node (ref "IC4") (pin "36") (pinfunction "FB5MC5_36") (pintype "bidirectional"))
    )
    (net (code "95") (name "/{slash}OE_CTRL_CLOCK") (class "Default")
      (node (ref "IC3") (pin "10") (pinfunction "OE_10") (pintype "input"))
      (node (ref "IC4") (pin "10") (pinfunction "FB2MC17_10") (pintype "bidirectional"))
    )
    (net (code "96") (name "/{slash}OE_IL") (class "Default")
      (node (ref "IC4") (pin "15") (pinfunction "FB1MC8_15") (pintype "bidirectional"))
      (node (ref "IC5") (pin "1") (pinfunction "OC_1") (pintype "input"))
    )
    (net (code "97") (name "/{slash}OE_RAMCS") (class "Default")
      (node (ref "IC3") (pin "4") (pinfunction "OE_4") (pintype "input"))
      (node (ref "IC4") (pin "17") (pinfunction "FB1MC11_17") (pintype "bidirectional"))
    )
    (net (code "98") (name "/{slash}OE_ROMCS") (class "Default")
      (node (ref "IC3") (pin "1") (pinfunction "OE_1") (pintype "input"))
      (node (ref "IC4") (pin "14") (pinfunction "FB1MC6_14") (pintype "bidirectional"))
    )
    (net (code "99") (name "/{slash}RAMCS") (class "Default")
      (node (ref "2A") (pin "1") (pinfunction "P_1") (pintype "passive"))
      (node (ref "IC3") (pin "6") (pinfunction "O_6") (pintype "tri_state"))
    )
    (net (code "100") (name "/{slash}RD") (class "Default")
      (node (ref "16A") (pin "1") (pinfunction "P_1") (pintype "passive"))
      (node (ref "IC4") (pin "49") (pinfunction "FB5MC17_49") (pintype "bidirectional"))
    )
    (net (code "101") (name "/{slash}RESET") (class "Default")
      (node (ref "21A") (pin "1") (pinfunction "P_1") (pintype "passive"))
      (node (ref "IC4") (pin "71") (pinfunction "FB8MC14_71") (pintype "bidirectional"))
      (node (ref "U$2") (pin "D6") (pinfunction "6_D6") (pintype "bidirectional"))
    )
    (net (code "102") (name "/{slash}RFSH") (class "Default")
      (node (ref "23A") (pin "1") (pinfunction "P_1") (pintype "passive"))
      (node (ref "IC4") (pin "64") (pinfunction "FB8MC5_64") (pintype "bidirectional"))
    )
    (net (code "103") (name "/{slash}ROMCS") (class "Default")
      (node (ref "23B") (pin "1") (pinfunction "P_1") (pintype "passive"))
      (node (ref "IC3") (pin "3") (pinfunction "O_3") (pintype "tri_state"))
    )
    (net (code "104") (name "/{slash}WAIT") (class "Default")
      (node (ref "19A") (pin "1") (pinfunction "P_1") (pintype "passive"))
      (node (ref "IC4") (pin "56") (pinfunction "FB7MC11_56") (pintype "bidirectional"))
      (node (ref "U$2") (pin "D42") (pinfunction "42_D42") (pintype "bidirectional"))
    )
    (net (code "105") (name "/{slash}WR") (class "Default")
      (node (ref "17A") (pin "1") (pinfunction "P_1") (pintype "passive"))
      (node (ref "IC4") (pin "52") (pinfunction "FB7MC5_52") (pintype "bidirectional"))
    )
    (net (code "106") (name "/{slash}WR'") (class "Default")
      (node (ref "IC1") (pin "29") (pinfunction "WE#_29") (pintype "input"))
      (node (ref "IC4") (pin "13") (pinfunction "FB1MC5_13") (pintype "bidirectional"))
      (node (ref "U$2") (pin "D41") (pinfunction "41_D41") (pintype "bidirectional"))
    )
    (net (code "107") (name "GND") (class "Default")
      (node (ref "4B") (pin "1") (pinfunction "P_1") (pintype "passive"))
      (node (ref "5B") (pin "1") (pinfunction "P_1") (pintype "passive"))
      (node (ref "C1") (pin "2") (pinfunction "2_2") (pintype "passive"))
      (node (ref "C12") (pin "2") (pinfunction "2_2") (pintype "passive"))
      (node (ref "C2") (pin "2") (pinfunction "2_2") (pintype "passive"))
      (node (ref "C3") (pin "2") (pinfunction "2_2") (pintype "passive"))
      (node (ref "C4") (pin "2") (pinfunction "2_2") (pintype "passive"))
      (node (ref "C8") (pin "-") (pinfunction "-_-") (pintype "passive"))
      (node (ref "C9") (pin "-") (pinfunction "-_-") (pintype "passive"))
      (node (ref "IC1") (pin "16") (pinfunction "VSS_16") (pintype "power_in"))
      (node (ref "IC2") (pin "1") (pinfunction "GND_1") (pintype "power_in"))
      (node (ref "IC4") (pin "100") (pinfunction "GND8_100") (pintype "power_in"))
      (node (ref "IC4") (pin "21") (pinfunction "GND1_21") (pintype "power_in"))
      (node (ref "IC4") (pin "31") (pinfunction "GND2_31") (pintype "power_in"))
      (node (ref "IC4") (pin "44") (pinfunction "GND3_44") (pintype "power_in"))
      (node (ref "IC4") (pin "62") (pinfunction "GND4_62") (pintype "power_in"))
      (node (ref "IC4") (pin "69") (pinfunction "GND5_69") (pintype "power_in"))
      (node (ref "IC4") (pin "75") (pinfunction "GND6_75") (pintype "power_in"))
      (node (ref "IC4") (pin "84") (pinfunction "GND7_84") (pintype "power_in"))
      (node (ref "IC7") (pin "2") (pinfunction "-IN_2") (pintype "input"))
      (node (ref "IC7") (pin "4") (pinfunction "GND_4") (pintype "power_in"))
      (node (ref "J1") (pin "SLEEVE") (pinfunction "SLEEVE_SLEEVE") (pintype "bidirectional"))
      (node (ref "JP2") (pin "2") (pinfunction "2_2") (pintype "passive"))
      (node (ref "JP4") (pin "2") (pinfunction "2_2") (pintype "passive"))
      (node (ref "LED2") (pin "2") (pinfunction "C_2") (pintype "bidirectional"))
      (node (ref "R1") (pin "P$1") (pinfunction "A_P$1") (pintype "passive"))
      (node (ref "R10") (pin "1") (pinfunction "1_1") (pintype "passive"))
      (node (ref "R16") (pin "1") (pinfunction "1_1") (pintype "passive"))
      (node (ref "R8") (pin "1") (pinfunction "1_1") (pintype "passive"))
      (node (ref "R9") (pin "1") (pinfunction "1_1") (pintype "passive"))
      (node (ref "S1") (pin "1") (pinfunction "S_1") (pintype "passive"))
      (node (ref "S1") (pin "2") (pinfunction "S1_2") (pintype "passive"))
      (node (ref "U$2") (pin "GND1") (pinfunction "GND._GND1") (pintype "bidirectional"))
      (node (ref "U$2") (pin "GND2") (pinfunction "GND.._GND2") (pintype "bidirectional"))
      (node (ref "U$3") (pin "GND") (pinfunction "GND.1_GND") (pintype "power_in"))
    )
    (net (code "108") (name "Net-(C4-Pad1)") (class "Default")
      (node (ref "C4") (pin "1") (pinfunction "1_1") (pintype "passive"))
      (node (ref "J1") (pin "RING") (pinfunction "RING_RING") (pintype "bidirectional"))
      (node (ref "J1") (pin "TIP") (pinfunction "TIP_TIP") (pintype "bidirectional"))
      (node (ref "R12") (pin "2") (pinfunction "2_2") (pintype "passive"))
    )
    (net (code "109") (name "Net-(C7-Pad+)") (class "Default")
      (node (ref "C7") (pin "+") (pinfunction "+_+") (pintype "passive"))
      (node (ref "IC7") (pin "1") (pinfunction "GAIN_1") (pintype "passive"))
    )
    (net (code "110") (name "Net-(C7-Pad-)") (class "Default")
      (node (ref "C7") (pin "-") (pinfunction "-_-") (pintype "passive"))
      (node (ref "IC7") (pin "8") (pinfunction "GAIN_8") (pintype "passive"))
    )
    (net (code "111") (name "Net-(C10-Pad-)") (class "Default")
      (node (ref "C10") (pin "-") (pinfunction "-_-") (pintype "passive"))
      (node (ref "JP4") (pin "1") (pinfunction "1_1") (pintype "passive"))
    )
    (net (code "112") (name "Net-(C11-Pad2)") (class "Default")
      (node (ref "C11") (pin "2") (pinfunction "2_2") (pintype "passive"))
      (node (ref "R16") (pin "2") (pinfunction "2_2") (pintype "passive"))
    )
    (net (code "113") (name "Net-(IC4-FB5MC8)") (class "Default")
      (node (ref "IC4") (pin "39") (pinfunction "FB5MC8_39") (pintype "bidirectional"))
      (node (ref "JP1") (pin "2") (pinfunction "2_2") (pintype "passive"))
    )
    (net (code "114") (name "Net-(IC4-FB6MC2)") (class "Default")
      (node (ref "IC4") (pin "74") (pinfunction "FB6MC2_74") (pintype "bidirectional"))
      (node (ref "PAD8") (pin "1") (pinfunction "P_1") (pintype "passive"))
    )
    (net (code "115") (name "Net-(IC4-FB8MC6)") (class "Default")
      (node (ref "IC4") (pin "65") (pinfunction "FB8MC6_65") (pintype "bidirectional"))
      (node (ref "PAD2") (pin "1") (pinfunction "P_1") (pintype "passive"))
    )
    (net (code "116") (name "Net-(IC4-FB8MC8)") (class "Default")
      (node (ref "IC4") (pin "66") (pinfunction "FB8MC8_66") (pintype "bidirectional"))
      (node (ref "PAD3") (pin "1") (pinfunction "P_1") (pintype "passive"))
    )
    (net (code "117") (name "Net-(IC4-FB8MC9)") (class "Default")
      (node (ref "IC4") (pin "67") (pinfunction "FB8MC9_67") (pintype "bidirectional"))
      (node (ref "PAD4") (pin "1") (pinfunction "P_1") (pintype "passive"))
    )
    (net (code "118") (name "Net-(IC4-FB8MC11)") (class "Default")
      (node (ref "IC4") (pin "68") (pinfunction "FB8MC11_68") (pintype "bidirectional"))
      (node (ref "PAD5") (pin "1") (pinfunction "P_1") (pintype "passive"))
    )
    (net (code "119") (name "Net-(IC4-FB8MC12)") (class "Default")
      (node (ref "IC4") (pin "70") (pinfunction "FB8MC12_70") (pintype "bidirectional"))
      (node (ref "PAD7") (pin "1") (pinfunction "P_1") (pintype "passive"))
    )
    (net (code "120") (name "Net-(IC4-FB8MC17)") (class "Default")
      (node (ref "IC4") (pin "73") (pinfunction "FB8MC17_73") (pintype "bidirectional"))
      (node (ref "PAD6") (pin "1") (pinfunction "P_1") (pintype "passive"))
    )
    (net (code "121") (name "Net-(IC4-GCK3)") (class "Default")
      (node (ref "IC4") (pin "27") (pinfunction "GCK3_27") (pintype "bidirectional"))
      (node (ref "PAD1") (pin "1") (pinfunction "P_1") (pintype "passive"))
    )
    (net (code "122") (name "Net-(IC7-+IN)") (class "Default")
      (node (ref "IC7") (pin "3") (pinfunction "+IN_3") (pintype "input"))
      (node (ref "R1") (pin "P$3") (pinfunction "S_P$3") (pintype "passive"))
    )
    (net (code "123") (name "Net-(IC7-BYPASS)") (class "Default")
      (node (ref "C12") (pin "1") (pinfunction "1_1") (pintype "passive"))
      (node (ref "IC7") (pin "7") (pinfunction "BYPASS_7") (pintype "passive"))
    )
    (net (code "124") (name "Net-(IC7-OUT)") (class "Default")
      (node (ref "C10") (pin "+") (pinfunction "+_+") (pintype "passive"))
      (node (ref "C11") (pin "1") (pinfunction "1_1") (pintype "passive"))
      (node (ref "IC7") (pin "5") (pinfunction "OUT_5") (pintype "output"))
    )
    (net (code "125") (name "Net-(IC8A-OC)") (class "Default")
      (node (ref "IC8") (pin "1") (pinfunction "OC_1") (pintype "input"))
      (node (ref "U$2") (pin "D7") (pinfunction "7_D7") (pintype "bidirectional"))
    )
    (net (code "126") (name "Net-(LED1-PadA)") (class "Default")
      (node (ref "LED1") (pin "A") (pinfunction "A_A") (pintype "passive"))
      (node (ref "R11") (pin "2") (pinfunction "2_2") (pintype "passive"))
    )
    (net (code "127") (name "Net-(LED2-BLU)") (class "Default")
      (node (ref "LED2") (pin "4") (pinfunction "BLU_4") (pintype "bidirectional"))
      (node (ref "R3") (pin "2") (pinfunction "2_2") (pintype "passive"))
    )
    (net (code "128") (name "Net-(LED2-GRN)") (class "Default")
      (node (ref "LED2") (pin "3") (pinfunction "GRN_3") (pintype "bidirectional"))
      (node (ref "R13") (pin "2") (pinfunction "2_2") (pintype "passive"))
    )
    (net (code "129") (name "Net-(LED2-RED)") (class "Default")
      (node (ref "LED2") (pin "1") (pinfunction "RED_1") (pintype "bidirectional"))
      (node (ref "R2") (pin "2") (pinfunction "2_2") (pintype "passive"))
    )
    (net (code "130") (name "Net-(R1-E)") (class "Default")
      (node (ref "J1") (pin "RSH") (pinfunction "RSH_RSH") (pintype "bidirectional"))
      (node (ref "J1") (pin "TSH") (pinfunction "TSH_TSH") (pintype "bidirectional"))
      (node (ref "R1") (pin "P$2") (pinfunction "E_P$2") (pintype "passive"))
    )
    (net (code "131") (name "Net-(S1-P)") (class "Default")
      (node (ref "S1") (pin "3") (pinfunction "P_3") (pintype "passive"))
      (node (ref "S1") (pin "4") (pinfunction "P1_4") (pintype "passive"))
      (node (ref "U$2") (pin "RST") (pinfunction "RESET_RST") (pintype "bidirectional"))
    )
    (net (code "132") (name "Net-(U$2-2)") (class "Default")
      (node (ref "R2") (pin "1") (pinfunction "1_1") (pintype "passive"))
      (node (ref "U$2") (pin "D2") (pinfunction "2_D2") (pintype "bidirectional"))
    )
    (net (code "133") (name "Net-(U$2-3)") (class "Default")
      (node (ref "R3") (pin "1") (pinfunction "1_1") (pintype "passive"))
      (node (ref "U$2") (pin "D3") (pinfunction "3_D3") (pintype "bidirectional"))
    )
    (net (code "134") (name "Net-(U$2-4)") (class "Default")
      (node (ref "R13") (pin "1") (pinfunction "1_1") (pintype "passive"))
      (node (ref "U$2") (pin "D4") (pinfunction "4_D4") (pintype "bidirectional"))
    )
    (net (code "135") (name "Net-(U$2-5V)") (class "Default")
      (node (ref "JP5") (pin "2") (pinfunction "2_2") (pintype "passive"))
      (node (ref "U$2") (pin "5V1") (pinfunction "5V_5V1") (pintype "bidirectional"))
      (node (ref "U$2") (pin "5V2") (pinfunction "5V.._5V2") (pintype "bidirectional"))
    )
    (net (code "136") (name "Net-(U$2-8)") (class "Default")
      (node (ref "R4") (pin "1") (pinfunction "1_1") (pintype "passive"))
      (node (ref "U$2") (pin "D8") (pinfunction "8_D8") (pintype "bidirectional"))
    )
    (net (code "137") (name "Net-(U$2-9)") (class "Default")
      (node (ref "R5") (pin "1") (pinfunction "1_1") (pintype "passive"))
      (node (ref "U$2") (pin "D9") (pinfunction "9_D9") (pintype "bidirectional"))
    )
    (net (code "138") (name "Net-(U$2-10)") (class "Default")
      (node (ref "R6") (pin "1") (pinfunction "1_1") (pintype "passive"))
      (node (ref "U$2") (pin "D10") (pinfunction "10_D10") (pintype "bidirectional"))
    )
    (net (code "139") (name "Net-(U$2-11)") (class "Default")
      (node (ref "R7") (pin "1") (pinfunction "1_1") (pintype "passive"))
      (node (ref "U$2") (pin "D11") (pinfunction "11_D11") (pintype "bidirectional"))
    )
    (net (code "140") (name "Net-(U$2-45)") (class "Default")
      (node (ref "R12") (pin "1") (pinfunction "1_1") (pintype "passive"))
      (node (ref "U$2") (pin "D45") (pinfunction "45_D45") (pintype "bidirectional"))
    )
    (net (code "141") (name "VCC") (class "Default")
      (node (ref "1B") (pin "1") (pinfunction "P_1") (pintype "passive"))
      (node (ref "C1") (pin "1") (pinfunction "1_1") (pintype "passive"))
      (node (ref "C2") (pin "1") (pinfunction "1_1") (pintype "passive"))
      (node (ref "C3") (pin "1") (pinfunction "1_1") (pintype "passive"))
      (node (ref "C8") (pin "+") (pinfunction "+_+") (pintype "passive"))
      (node (ref "IC1") (pin "32") (pinfunction "VCC_32") (pintype "power_in"))
      (node (ref "IC2") (pin "3") (pinfunction "VIN_3") (pintype "input"))
      (node (ref "IC3") (pin "12") (pinfunction "I_12") (pintype "input"))
      (node (ref "IC3") (pin "13") (pinfunction "OE_13") (pintype "input"))
      (node (ref "IC3") (pin "2") (pinfunction "I_2") (pintype "input"))
      (node (ref "IC3") (pin "5") (pinfunction "I_5") (pintype "input"))
      (node (ref "JP5") (pin "1") (pinfunction "1_1") (pintype "passive"))
      (node (ref "R11") (pin "1") (pinfunction "1_1") (pintype "passive"))
      (node (ref "U$3") (pin "VCC") (pinfunction "5V_VCC") (pintype "power_in"))
    )
    (net (code "142") (name "unconnected-(IC3D-O-Pad11)") (class "Default")
      (node (ref "IC3") (pin "11") (pinfunction "O_11") (pintype "tri_state"))
    )
    (net (code "143") (name "unconnected-(U$2-0(RX)-PadRX)") (class "Default")
      (node (ref "U$2") (pin "RX") (pinfunction "0(RX)_RX") (pintype "bidirectional"))
    )
    (net (code "144") (name "unconnected-(U$2-1(TX)-PadTX)") (class "Default")
      (node (ref "U$2") (pin "TX") (pinfunction "1(TX)_TX") (pintype "bidirectional"))
    )
    (net (code "145") (name "unconnected-(U$2-3.3V-Pad3V3_1)") (class "Default")
      (node (ref "U$2") (pin "3V3_1") (pinfunction "3.3V_3V3_1") (pintype "bidirectional"))
    )
    (net (code "146") (name "unconnected-(U$2-3.3V..-Pad3V3_2)") (class "Default")
      (node (ref "U$2") (pin "3V3_2") (pinfunction "3.3V.._3V3_2") (pintype "bidirectional"))
    )
    (net (code "147") (name "unconnected-(U$2-Pad+5V_)") (class "Default")
      (node (ref "U$2") (pin "+5V_") (pinfunction "+5V__+5V_") (pintype "bidirectional"))
    )
    (net (code "148") (name "unconnected-(U$2-PadAREF)") (class "Default")
      (node (ref "U$2") (pin "AREF") (pinfunction "AREF_AREF") (pintype "bidirectional"))
    )
    (net (code "149") (name "unconnected-(U$2-PadGND__)") (class "Default")
      (node (ref "U$2") (pin "GND__") (pinfunction "GND___GND__") (pintype "bidirectional"))
    )
    (net (code "150") (name "unconnected-(U$2-PadMISO)") (class "Default")
      (node (ref "U$2") (pin "MISO") (pinfunction "MISO_MISO") (pintype "bidirectional"))
    )
    (net (code "151") (name "unconnected-(U$2-PadMOSI)") (class "Default")
      (node (ref "U$2") (pin "MOSI") (pinfunction "MOSI_MOSI") (pintype "bidirectional"))
    )
    (net (code "152") (name "unconnected-(U$2-PadRESET.)") (class "Default")
      (node (ref "U$2") (pin "RESET.") (pinfunction "RESET._RESET.") (pintype "bidirectional"))
    )
    (net (code "153") (name "unconnected-(U$2-PadSCK)") (class "Default")
      (node (ref "U$2") (pin "SCK") (pinfunction "SCK_SCK") (pintype "bidirectional"))
    )
  )
)
